# I2C_Step_12V_List1.net
KiCad netlist of a schematic drawn in Altium Designer
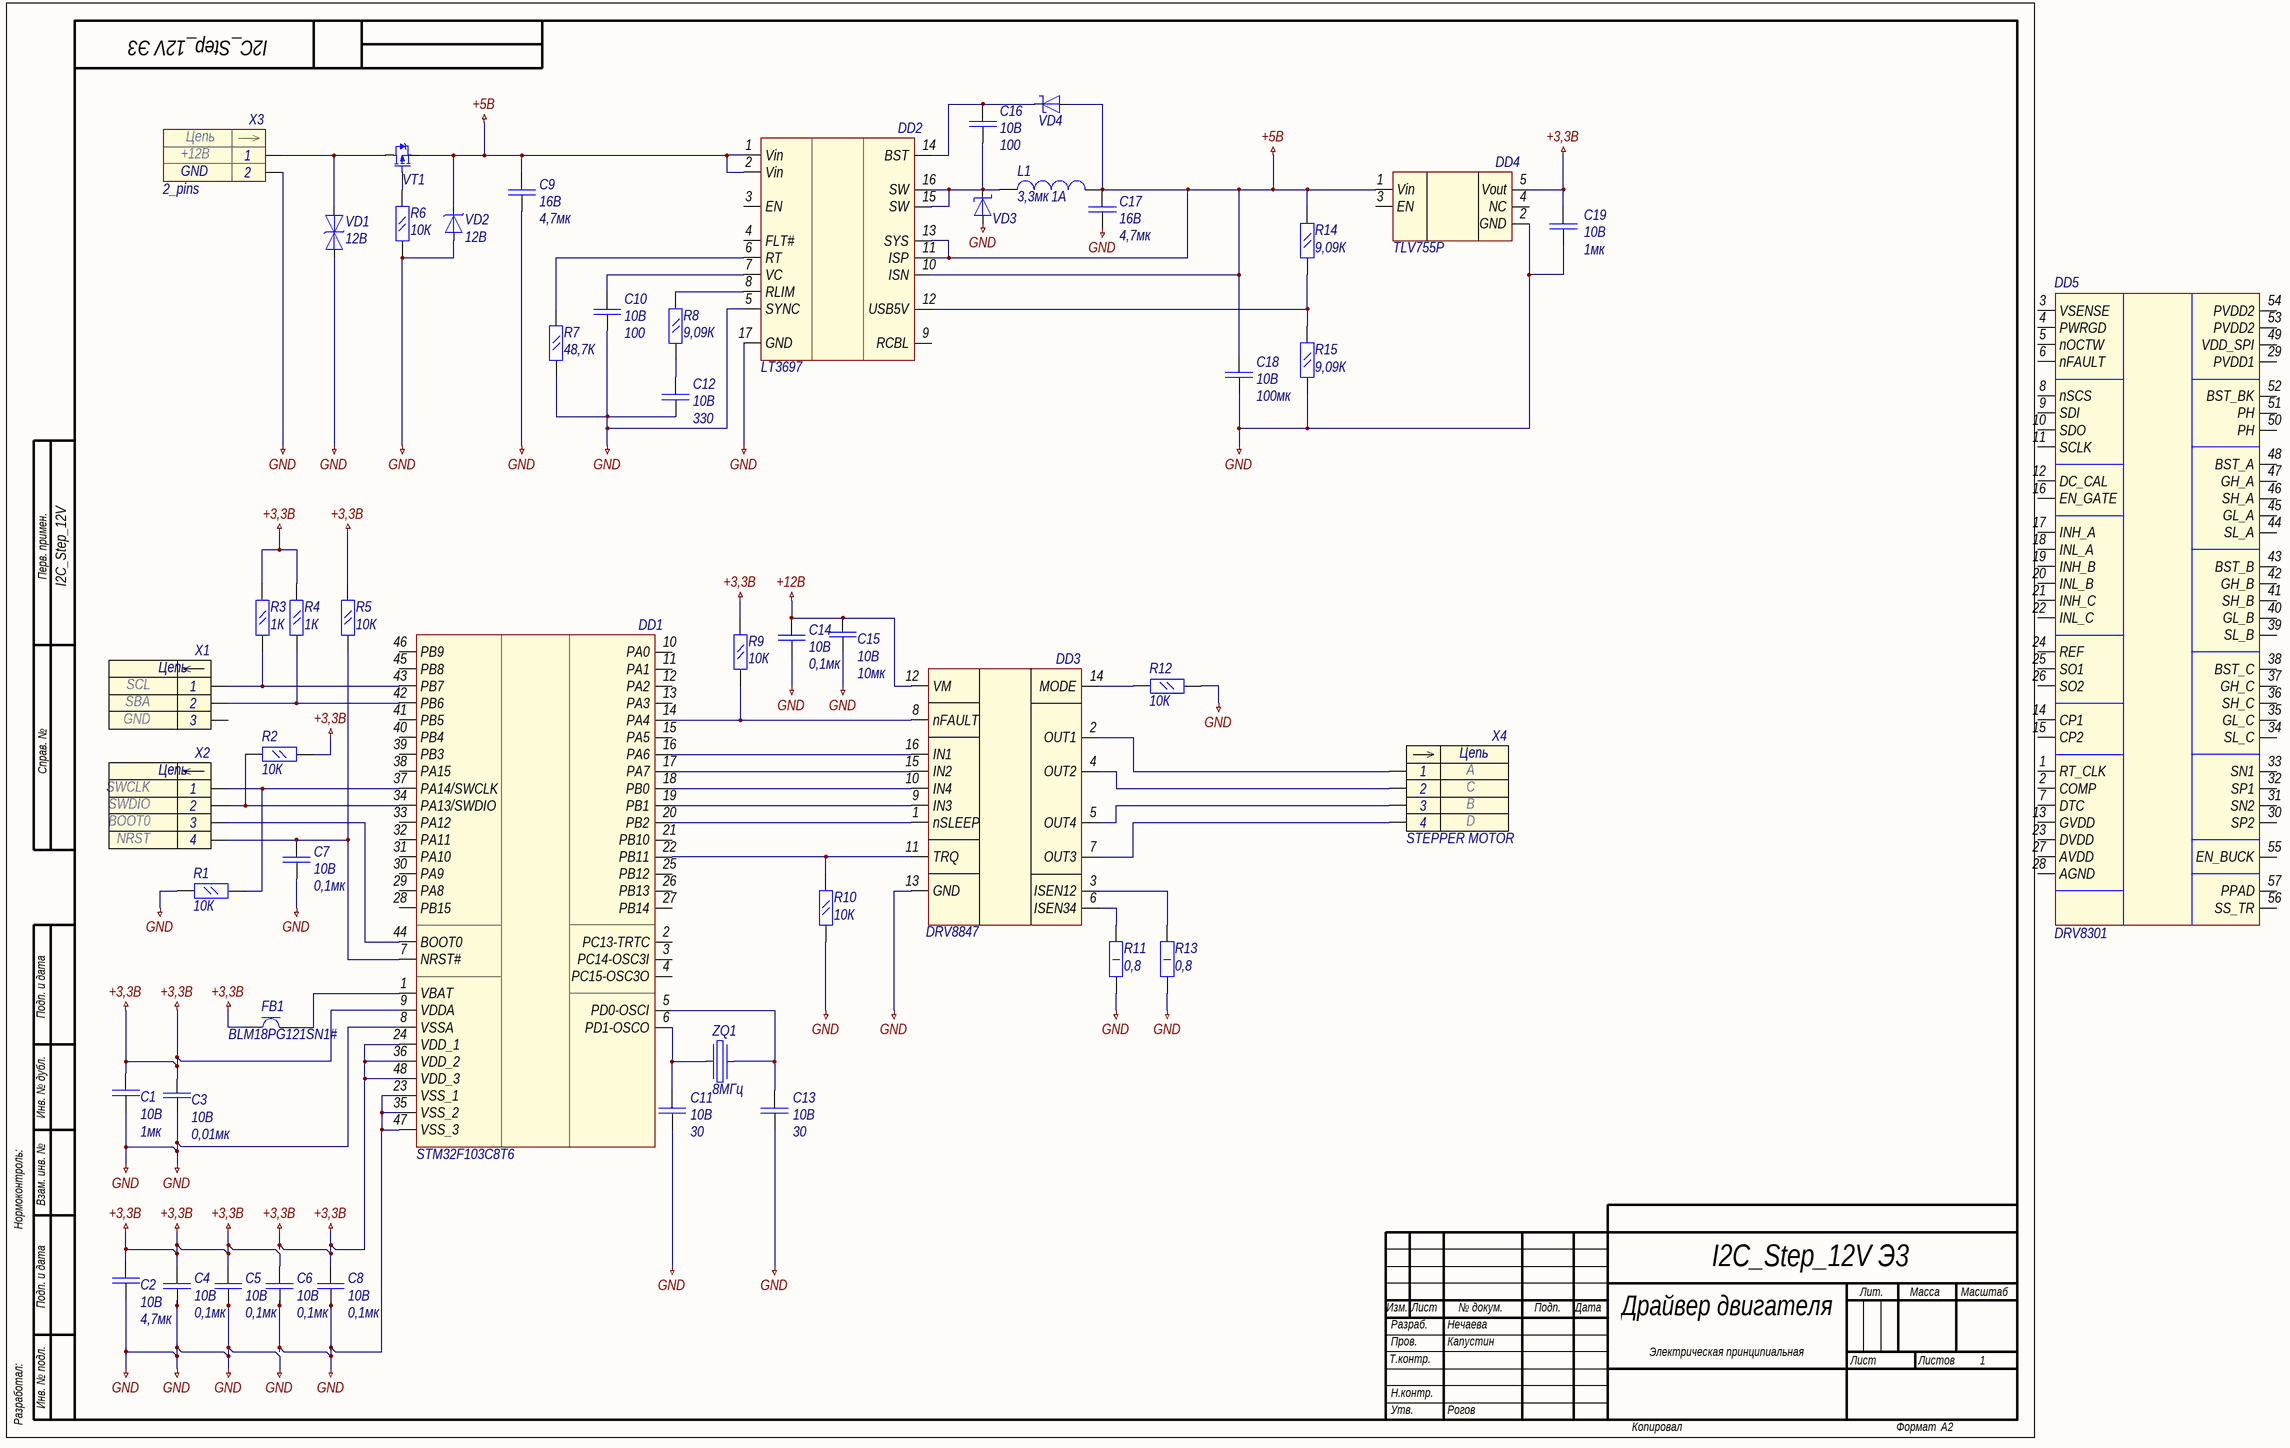
[diagram p0: I2C_Step_12V_List1.SchDoc]

(export (version "E")
  (design (tool "Eeschema 10.0.6"))
  (components
    (comp (ref "C1")
      (value "Capacitor")
      (footprint "CH0201C")
      (fields (field (name "VOLTAGE") "10В") (field (name "CAPACITANCE") "1мк"))
      (libsource (lib "GOST_Capacitors") (part "Capacitor"))
    )
    (comp (ref "C2")
      (value "Capacitor")
      (footprint "CH0402C")
      (fields (field (name "VOLTAGE") "10В") (field (name "CAPACITANCE") "4,7мк"))
      (libsource (lib "GOST_Capacitors") (part "Capacitor"))
    )
    (comp (ref "C3")
      (value "Capacitor")
      (footprint "CH0402C")
      (fields (field (name "VOLTAGE") "10В") (field (name "CAPACITANCE") "0,01мк"))
      (libsource (lib "") (part "Capacitor_1"))
    )
    (comp (ref "C4")
      (value "Capacitor")
      (footprint "CH0402C")
      (fields (field (name "VOLTAGE") "10В") (field (name "CAPACITANCE") "0,1мк"))
      (libsource (lib "GOST_Capacitors") (part "Capacitor"))
    )
    (comp (ref "C5")
      (value "Capacitor")
      (footprint "CH0402C")
      (fields (field (name "VOLTAGE") "10В") (field (name "CAPACITANCE") "0,1мк"))
      (libsource (lib "GOST_Capacitors") (part "Capacitor"))
    )
    (comp (ref "C6")
      (value "Capacitor")
      (footprint "CH0402C")
      (fields (field (name "VOLTAGE") "10В") (field (name "CAPACITANCE") "0,1мк"))
      (libsource (lib "GOST_Capacitors") (part "Capacitor"))
    )
    (comp (ref "C7")
      (value "Capacitor")
      (footprint "CH0402C")
      (fields (field (name "VOLTAGE") "10В") (field (name "CAPACITANCE") "0,1мк"))
      (libsource (lib "GOST_Capacitors") (part "Capacitor"))
    )
    (comp (ref "C8")
      (value "Capacitor")
      (footprint "CH0402C")
      (fields (field (name "VOLTAGE") "10В") (field (name "CAPACITANCE") "0,1мк"))
      (libsource (lib "GOST_Capacitors") (part "Capacitor"))
    )
    (comp (ref "C9")
      (value "Capacitor")
      (footprint "CH0603C")
      (fields (field (name "VOLTAGE") "16В") (field (name "CAPACITANCE") "4,7мк"))
      (libsource (lib "GOST_Capacitors") (part "Capacitor"))
    )
    (comp (ref "C10")
      (value "Capacitor")
      (footprint "CH0201C")
      (fields (field (name "VOLTAGE") "10В") (field (name "CAPACITANCE") "100"))
      (libsource (lib "GOST_Capacitors") (part "Capacitor"))
    )
    (comp (ref "C11")
      (value "Capacitor")
      (footprint "CH0201C")
      (fields (field (name "VOLTAGE") "10В") (field (name "CAPACITANCE") "30"))
      (libsource (lib "GOST_Capacitors") (part "Capacitor"))
    )
    (comp (ref "C12")
      (value "Capacitor")
      (footprint "CH0402C")
      (fields (field (name "VOLTAGE") "10В") (field (name "CAPACITANCE") "330"))
      (libsource (lib "GOST_Capacitors") (part "Capacitor"))
    )
    (comp (ref "C13")
      (value "Capacitor")
      (footprint "CH0201C")
      (fields (field (name "VOLTAGE") "10В") (field (name "CAPACITANCE") "30"))
      (libsource (lib "GOST_Capacitors") (part "Capacitor"))
    )
    (comp (ref "C14")
      (value "Capacitor")
      (footprint "CH0402C")
      (fields (field (name "VOLTAGE") "10В") (field (name "CAPACITANCE") "0,1мк"))
      (libsource (lib "GOST_Capacitors") (part "Capacitor"))
    )
    (comp (ref "C15")
      (value "Capacitor")
      (footprint "CH0402C")
      (fields (field (name "VOLTAGE") "10В") (field (name "CAPACITANCE") "10мк"))
      (libsource (lib "") (part "Capacitor_1"))
    )
    (comp (ref "C16")
      (value "Capacitor")
      (footprint "CH0201C")
      (fields (field (name "VOLTAGE") "10В") (field (name "CAPACITANCE") "100"))
      (libsource (lib "GOST_Capacitors") (part "Capacitor"))
    )
    (comp (ref "C17")
      (value "Capacitor")
      (footprint "CH0603C")
      (fields (field (name "VOLTAGE") "16В") (field (name "CAPACITANCE") "4,7мк"))
      (libsource (lib "GOST_Capacitors") (part "Capacitor"))
    )
    (comp (ref "C18")
      (value "Capacitor")
      (footprint "CH1206C")
      (fields (field (name "VOLTAGE") "10В") (field (name "CAPACITANCE") "100мк"))
      (libsource (lib "GOST_Capacitors") (part "Capacitor"))
    )
    (comp (ref "C19")
      (value "Capacitor")
      (footprint "CH0201C")
      (fields (field (name "VOLTAGE") "10В") (field (name "CAPACITANCE") "1мк"))
      (libsource (lib "GOST_Capacitors") (part "Capacitor"))
    )
    (comp (ref "DD1")
      (value "STM32F103C8T6")
      (footprint "STM32F103 48pins")
      (libsource (lib "GOST_lib_devices") (part "STM32"))
    )
    (comp (ref "DD2")
      (value "LT3697")
      (footprint "LT3697")
      (description "6~18 to 5")
      (libsource (lib "GOST_lib_devices") (part "LT3697"))
    )
    (comp (ref "DD3") (value "DRV8847") (libsource (lib "GOST_lib_devices") (part "DRV8847")))
    (comp (ref "DD4")
      (value "TLV755P")
      (footprint "SOT23-5")
      (libsource (lib "GOST_lib_devices") (part "LDO +3.3V"))
    )
    (comp (ref "DD5") (value "DRV8301") (libsource (lib "GOST_lib_devices") (part "DRV8301")))
    (comp (ref "FB1")
      (value "Ferrite bead")
      (footprint "CH0603L")
      (fields (field (name "MODEL") "BLM18PG121SN1#"))
      (libsource (lib "GOST_Inductors") (part "Ferrite bead"))
    )
    (comp (ref "L1")
      (value "*")
      (footprint "CH0805L")
      (fields (field (name "MAX CURRENT") "1А") (field (name "INDUCTANCE") "3,3мк"))
      (libsource (lib "GOST_Inductors") (part "Inductor"))
    )
    (comp (ref "R1")
      (value "Res_0.125")
      (footprint "CH0402R")
      (fields (field (name "IMPEDANCE") "10К"))
      (libsource (lib "GOST_Resistors") (part "Res_0.125"))
    )
    (comp (ref "R2")
      (value "Res_0.125")
      (footprint "CH0402R")
      (fields (field (name "IMPEDANCE") "10К"))
      (libsource (lib "GOST_Resistors") (part "Res_0.125"))
    )
    (comp (ref "R3")
      (value "Res_0.125")
      (footprint "CH0402R")
      (fields (field (name "IMPEDANCE") "1К"))
      (libsource (lib "GOST_Resistors") (part "Res_0.125"))
    )
    (comp (ref "R4")
      (value "Res_0.125")
      (footprint "CH0402R")
      (fields (field (name "IMPEDANCE") "1К"))
      (libsource (lib "GOST_Resistors") (part "Res_0.125"))
    )
    (comp (ref "R5")
      (value "Res_0.125")
      (footprint "CH0402R")
      (fields (field (name "IMPEDANCE") "10К"))
      (libsource (lib "GOST_Resistors") (part "Res_0.125"))
    )
    (comp (ref "R6")
      (value "Res_0.125")
      (footprint "CH0402R")
      (fields (field (name "IMPEDANCE") "10К"))
      (libsource (lib "GOST_Resistors") (part "Res_0.125"))
    )
    (comp (ref "R7")
      (value "Res_0.125")
      (footprint "CH0805R")
      (fields (field (name "IMPEDANCE") "48,7К"))
      (libsource (lib "GOST_Resistors") (part "Res_0.125"))
    )
    (comp (ref "R8")
      (value "Res_0.125")
      (footprint "CH0805R")
      (fields (field (name "IMPEDANCE") "9,09К"))
      (libsource (lib "GOST_Resistors") (part "Res_0.125"))
    )
    (comp (ref "R9")
      (value "Res_0.125")
      (footprint "CH0402R")
      (fields (field (name "IMPEDANCE") "10К"))
      (libsource (lib "GOST_Resistors") (part "Res_0.125"))
    )
    (comp (ref "R10")
      (value "Res_0.125")
      (footprint "CH0402R")
      (fields (field (name "IMPEDANCE") "10К"))
      (libsource (lib "GOST_Resistors") (part "Res_0.125"))
    )
    (comp (ref "R11")
      (value "Res_1")
      (footprint "CH2010R")
      (fields (field (name "POWER") "1Вт") (field (name "IMPEDANCE") "0,8"))
      (libsource (lib "GOST_Resistors") (part "Res_1"))
    )
    (comp (ref "R12")
      (value "Res_0.125")
      (footprint "CH0402R")
      (fields (field (name "IMPEDANCE") "10К"))
      (libsource (lib "GOST_Resistors") (part "Res_0.125"))
    )
    (comp (ref "R13")
      (value "Res_1")
      (footprint "CH2010R")
      (fields (field (name "POWER") "1Вт") (field (name "IMPEDANCE") "0,8"))
      (libsource (lib "GOST_Resistors") (part "Res_1"))
    )
    (comp (ref "R14")
      (value "Res_0.125")
      (footprint "CH0805R")
      (fields (field (name "IMPEDANCE") "9,09К"))
      (libsource (lib "GOST_Resistors") (part "Res_0.125"))
    )
    (comp (ref "R15")
      (value "Res_0.125")
      (footprint "CH0805R")
      (fields (field (name "IMPEDANCE") "9,09К"))
      (libsource (lib "GOST_Resistors") (part "Res_0.125"))
    )
    (comp (ref "VD1")
      (value "TVS-diod_simmetrical")
      (footprint "CH0201L")
      (fields (field (name "MANUFACTURER") "Littelfuse") (field (name "CLAMPING VOLTAGE") "12В"))
      (libsource (lib "GOST_Diodes") (part "TVS-diod_simmetrical"))
    )
    (comp (ref "VD2")
      (value "TVS-diod_directed")
      (footprint "DO214AA")
      (fields (field (name "MANUFACTURER") "Bourns") (field (name "CLAMPING_VOLTAGE") "12В"))
      (libsource (lib "GOST_Diodes") (part "TVS-diod_directed"))
    )
    (comp (ref "VD3")
      (value "Diod Schottky")
      (footprint "DO214AA")
      (fields (field (name "MANUFACTURER") "Rectron"))
      (libsource (lib "GOST_Diodes") (part "Diod Schottky"))
    )
    (comp (ref "VD4")
      (value "Diod Schottky")
      (footprint "SOT23_132")
      (fields (field (name "MANUFACTURER") "Toshiba"))
      (libsource (lib "GOST_Diodes") (part "Diod Schottky"))
    )
    (comp (ref "VT1")
      (value "*")
      (footprint "SOT23_132")
      (libsource (lib "GOST_Transistors") (part "P-Channel"))
    )
    (comp (ref "X1")
      (value "3_pins")
      (footprint "CON: PBS-3")
      (fields (field (name "2") "SBA") (field (name "3") "GND") (field (name "1") "SCL"))
      (libsource (lib "GOST_lib_connectors") (part "3_pins"))
    )
    (comp (ref "X2")
      (value "4_pins")
      (footprint "CON: CWF-4R")
      (fields
        (field (name "2") "SWDIO")
        (field (name "3") "BOOT0")
        (field (name "1") "SWCLK")
        (field (name "4") "NRST")
      )
      (libsource (lib "") (part "4_pins_1"))
    )
    (comp (ref "X3")
      (value "2_pins")
      (footprint "CON: 163-179PH-EX")
      (fields (field (name "VCC") "+12В"))
      (libsource (lib "GOST_lib_connectors") (part "2_pins"))
    )
    (comp (ref "X4")
      (value "STEPPER MOTOR")
      (footprint "CON: CWF-4R")
      (description "Bipolar Stepper Motor 200 Step 0.35A 12VDC")
      (fields (field (name "2") "C") (field (name "3") "B") (field (name "1") "A") (field (name "4") "D"))
      (libsource (lib "GOST_lib_connectors") (part "4_pins"))
    )
    (comp (ref "ZQ1")
      (value "Oscillator")
      (footprint "OSC: 5032")
      (fields (field (name "FREQ") "8МГц"))
      (libsource (lib "GOST_Miscelanuious") (part "Oscillator"))
    )
  )
  (nets
    (net (code "1") (name "+3,3В") (class "Default")
      (node (ref "C1") (pin "2") (pinfunction "C1-_2") (pintype "power_in"))
      (node (ref "C19") (pin "1") (pinfunction "C1+_1") (pintype "power_in"))
      (node (ref "C2") (pin "2") (pinfunction "C1-_2") (pintype "power_in"))
      (node (ref "C3") (pin "1") (pinfunction "С+_1") (pintype "power_in"))
      (node (ref "C4") (pin "1") (pinfunction "C1+_1") (pintype "power_in"))
      (node (ref "C5") (pin "1") (pinfunction "C1+_1") (pintype "power_in"))
      (node (ref "C6") (pin "1") (pinfunction "C1+_1") (pintype "power_in"))
      (node (ref "C8") (pin "1") (pinfunction "C1+_1") (pintype "power_in"))
      (node (ref "DD1") (pin "24") (pinfunction "VDD_1_24") (pintype "passive"))
      (node (ref "DD1") (pin "36") (pinfunction "VDD_2_36") (pintype "passive"))
      (node (ref "DD1") (pin "48") (pinfunction "VDD_3_48") (pintype "passive"))
      (node (ref "DD1") (pin "9") (pinfunction "VDDA_9") (pintype "passive"))
      (node (ref "DD4") (pin "5") (pinfunction "Vout_5") (pintype "power_in"))
      (node (ref "FB1") (pin "1") (pintype "power_in"))
      (node (ref "R2") (pin "1") (pinfunction "C1-_1") (pintype "power_in"))
      (node (ref "R3") (pin "1") (pinfunction "C1-_1") (pintype "power_in"))
      (node (ref "R4") (pin "1") (pinfunction "C1-_1") (pintype "power_in"))
      (node (ref "R5") (pin "1") (pinfunction "C1-_1") (pintype "power_in"))
      (node (ref "R9") (pin "1") (pinfunction "C1-_1") (pintype "power_in"))
    )
    (net (code "2") (name "+5В") (class "Default")
      (node (ref "C17") (pin "1") (pinfunction "C1+_1") (pintype "power_in"))
      (node (ref "C18") (pin "1") (pinfunction "C1+_1") (pintype "power_in"))
      (node (ref "C9") (pin "1") (pinfunction "C1+_1") (pintype "power_in"))
      (node (ref "DD2") (pin "1") (pinfunction "Vin_1") (pintype "power_in"))
      (node (ref "DD2") (pin "10") (pinfunction "ISN_10") (pintype "power_in"))
      (node (ref "DD2") (pin "11") (pinfunction "ISP_11") (pintype "power_in"))
      (node (ref "DD2") (pin "13") (pinfunction "SYS_13") (pintype "power_in"))
      (node (ref "DD2") (pin "2") (pinfunction "Vin_2") (pintype "power_in"))
      (node (ref "DD4") (pin "1") (pinfunction "Vin_1") (pintype "power_in"))
      (node (ref "L1") (pin "2") (pinfunction "14_2") (pintype "power_in"))
      (node (ref "R14") (pin "1") (pinfunction "C1-_1") (pintype "power_in"))
      (node (ref "VD2") (pin "2") (pinfunction "C_2") (pintype "passive"))
      (node (ref "VD4") (pin "1") (pinfunction "1_1") (pintype "passive"))
      (node (ref "VT1") (pin "3") (pinfunction "S_3") (pintype "passive"))
    )
    (net (code "3") (name "+12В") (class "Default")
      (node (ref "C14") (pin "1") (pinfunction "C1+_1") (pintype "power_in"))
      (node (ref "C15") (pin "1") (pinfunction "С+_1") (pintype "power_in"))
      (node (ref "DD3") (pin "12") (pinfunction "VM_12") (pintype "power_in"))
    )
    (net (code "4") (name "GND") (class "Default")
      (node (ref "C1") (pin "1") (pinfunction "C1+_1") (pintype "power_in"))
      (node (ref "C10") (pin "2") (pinfunction "C1-_2") (pintype "power_in"))
      (node (ref "C11") (pin "2") (pinfunction "C1-_2") (pintype "power_in"))
      (node (ref "C12") (pin "2") (pinfunction "C1-_2") (pintype "power_in"))
      (node (ref "C13") (pin "2") (pinfunction "C1-_2") (pintype "power_in"))
      (node (ref "C14") (pin "2") (pinfunction "C1-_2") (pintype "power_in"))
      (node (ref "C15") (pin "2") (pinfunction "С-_2") (pintype "power_in"))
      (node (ref "C17") (pin "2") (pinfunction "C1-_2") (pintype "power_in"))
      (node (ref "C18") (pin "2") (pinfunction "C1-_2") (pintype "power_in"))
      (node (ref "C19") (pin "2") (pinfunction "C1-_2") (pintype "power_in"))
      (node (ref "C2") (pin "1") (pinfunction "C1+_1") (pintype "power_in"))
      (node (ref "C3") (pin "2") (pinfunction "С-_2") (pintype "power_in"))
      (node (ref "C4") (pin "2") (pinfunction "C1-_2") (pintype "power_in"))
      (node (ref "C5") (pin "2") (pinfunction "C1-_2") (pintype "power_in"))
      (node (ref "C6") (pin "2") (pinfunction "C1-_2") (pintype "power_in"))
      (node (ref "C7") (pin "2") (pinfunction "C1-_2") (pintype "power_in"))
      (node (ref "C8") (pin "2") (pinfunction "C1-_2") (pintype "power_in"))
      (node (ref "C9") (pin "2") (pinfunction "C1-_2") (pintype "power_in"))
      (node (ref "DD1") (pin "23") (pinfunction "VSS_1_23") (pintype "passive"))
      (node (ref "DD1") (pin "35") (pinfunction "VSS_2_35") (pintype "passive"))
      (node (ref "DD1") (pin "47") (pinfunction "VSS_3_47") (pintype "passive"))
      (node (ref "DD1") (pin "8") (pinfunction "VSSA_8") (pintype "passive"))
      (node (ref "DD2") (pin "17") (pinfunction "GND_17") (pintype "power_in"))
      (node (ref "DD2") (pin "5") (pinfunction "SYNC_5") (pintype "power_in"))
      (node (ref "DD3") (pin "13") (pinfunction "GND_13") (pintype "power_in"))
      (node (ref "DD4") (pin "2") (pinfunction "GND_2") (pintype "power_in"))
      (node (ref "R1") (pin "2") (pinfunction "C1-_2") (pintype "power_in"))
      (node (ref "R10") (pin "2") (pinfunction "C1-_2") (pintype "power_in"))
      (node (ref "R11") (pin "1") (pinfunction "*_1") (pintype "power_in"))
      (node (ref "R12") (pin "1") (pinfunction "C1-_1") (pintype "power_in"))
      (node (ref "R13") (pin "1") (pinfunction "*_1") (pintype "power_in"))
      (node (ref "R15") (pin "2") (pinfunction "C1-_2") (pintype "power_in"))
      (node (ref "R6") (pin "1") (pinfunction "C1-_1") (pintype "power_in"))
      (node (ref "R7") (pin "2") (pinfunction "C1-_2") (pintype "power_in"))
      (node (ref "VD1") (pin "1") (pinfunction "A_1") (pintype "passive"))
      (node (ref "VD2") (pin "1") (pinfunction "A_1") (pintype "passive"))
      (node (ref "VD3") (pin "1") (pinfunction "1_1") (pintype "passive"))
      (node (ref "X3") (pin "2") (pinfunction "2_2") (pintype "passive"))
    )
    (net (code "5") (name "Net-(C7-C1+)") (class "Default")
      (node (ref "C7") (pin "1") (pinfunction "C1+_1") (pintype "power_in"))
      (node (ref "DD1") (pin "7") (pinfunction "NRST#_7") (pintype "passive"))
      (node (ref "R5") (pin "2") (pinfunction "C1-_2") (pintype "power_in"))
      (node (ref "X2") (pin "4") (pinfunction "4_4") (pintype "passive"))
    )
    (net (code "6") (name "Net-(C10-C1+)") (class "Default")
      (node (ref "C10") (pin "1") (pinfunction "C1+_1") (pintype "power_in"))
      (node (ref "DD2") (pin "7") (pinfunction "VC_7") (pintype "power_in"))
    )
    (net (code "7") (name "Net-(C11-C1+)") (class "Default")
      (node (ref "C11") (pin "1") (pinfunction "C1+_1") (pintype "power_in"))
      (node (ref "DD1") (pin "6") (pinfunction "PD1-OSCO_6") (pintype "passive"))
      (node (ref "ZQ1") (pin "1") (pintype "passive"))
    )
    (net (code "8") (name "Net-(C12-C1+)") (class "Default")
      (node (ref "C12") (pin "1") (pinfunction "C1+_1") (pintype "power_in"))
      (node (ref "R8") (pin "2") (pinfunction "C1-_2") (pintype "power_in"))
    )
    (net (code "9") (name "Net-(C13-C1+)") (class "Default")
      (node (ref "C13") (pin "1") (pinfunction "C1+_1") (pintype "power_in"))
      (node (ref "DD1") (pin "5") (pinfunction "PD0-OSCI_5") (pintype "passive"))
      (node (ref "ZQ1") (pin "3") (pintype "passive"))
    )
    (net (code "10") (name "Net-(C16-C1+)") (class "Default")
      (node (ref "C16") (pin "1") (pinfunction "C1+_1") (pintype "power_in"))
      (node (ref "DD2") (pin "14") (pinfunction "BST_14") (pintype "power_in"))
      (node (ref "VD4") (pin "2") (pinfunction "2_2") (pintype "passive"))
    )
    (net (code "11") (name "Net-(C16-C1-)") (class "Default")
      (node (ref "C16") (pin "2") (pinfunction "C1-_2") (pintype "power_in"))
      (node (ref "DD2") (pin "15") (pinfunction "SW_15") (pintype "power_in"))
      (node (ref "DD2") (pin "16") (pinfunction "SW_16") (pintype "power_in"))
      (node (ref "L1") (pin "1") (pinfunction "C1-_1") (pintype "power_in"))
      (node (ref "VD3") (pin "2") (pinfunction "2_2") (pintype "passive"))
    )
    (net (code "12") (name "Net-(DD1-BOOT0)") (class "Default")
      (node (ref "DD1") (pin "44") (pinfunction "BOOT0_44") (pintype "passive"))
      (node (ref "X2") (pin "3") (pinfunction "3_3") (pintype "passive"))
    )
    (net (code "13") (name "Net-(DD1-PA4)") (class "Default")
      (node (ref "DD1") (pin "14") (pinfunction "PA4_14") (pintype "passive"))
      (node (ref "DD3") (pin "8") (pinfunction "nFAULT_8") (pintype "power_in"))
      (node (ref "R9") (pin "2") (pinfunction "C1-_2") (pintype "power_in"))
    )
    (net (code "14") (name "Net-(DD1-PA6)") (class "Default")
      (node (ref "DD1") (pin "16") (pinfunction "PA6_16") (pintype "passive"))
      (node (ref "DD3") (pin "16") (pinfunction "IN1_16") (pintype "power_in"))
    )
    (net (code "15") (name "Net-(DD1-PA7)") (class "Default")
      (node (ref "DD1") (pin "17") (pinfunction "PA7_17") (pintype "passive"))
      (node (ref "DD3") (pin "15") (pinfunction "IN2_15") (pintype "power_in"))
    )
    (net (code "16") (name "Net-(DD1-PA13{slash}SWDIO)") (class "Default")
      (node (ref "DD1") (pin "34") (pinfunction "PA13/SWDIO_34") (pintype "passive"))
      (node (ref "R2") (pin "2") (pinfunction "C1-_2") (pintype "power_in"))
      (node (ref "X2") (pin "2") (pinfunction "2_2") (pintype "passive"))
    )
    (net (code "17") (name "Net-(DD1-PA14{slash}SWCLK)") (class "Default")
      (node (ref "DD1") (pin "37") (pinfunction "PA14/SWCLK_37") (pintype "passive"))
      (node (ref "R1") (pin "1") (pinfunction "C1-_1") (pintype "power_in"))
      (node (ref "X2") (pin "1") (pinfunction "1_1") (pintype "passive"))
    )
    (net (code "18") (name "Net-(DD1-PB0)") (class "Default")
      (node (ref "DD1") (pin "18") (pinfunction "PB0_18") (pintype "passive"))
      (node (ref "DD3") (pin "10") (pinfunction "IN4_10") (pintype "power_in"))
    )
    (net (code "19") (name "Net-(DD1-PB1)") (class "Default")
      (node (ref "DD1") (pin "19") (pinfunction "PB1_19") (pintype "passive"))
      (node (ref "DD3") (pin "9") (pinfunction "IN3_9") (pintype "power_in"))
    )
    (net (code "20") (name "Net-(DD1-PB2)") (class "Default")
      (node (ref "DD1") (pin "20") (pinfunction "PB2_20") (pintype "passive"))
      (node (ref "DD3") (pin "1") (pinfunction "nSLEEP_1") (pintype "power_in"))
    )
    (net (code "21") (name "Net-(DD1-PB6)") (class "Default")
      (node (ref "DD1") (pin "42") (pinfunction "PB6_42") (pintype "passive"))
      (node (ref "R4") (pin "2") (pinfunction "C1-_2") (pintype "power_in"))
      (node (ref "X1") (pin "2") (pinfunction "2_2") (pintype "passive"))
    )
    (net (code "22") (name "Net-(DD1-PB7)") (class "Default")
      (node (ref "DD1") (pin "43") (pinfunction "PB7_43") (pintype "passive"))
      (node (ref "R3") (pin "2") (pinfunction "C1-_2") (pintype "power_in"))
      (node (ref "X1") (pin "1") (pinfunction "1_1") (pintype "passive"))
    )
    (net (code "23") (name "Net-(DD1-PB11)") (class "Default")
      (node (ref "DD1") (pin "22") (pinfunction "PB11_22") (pintype "passive"))
      (node (ref "DD3") (pin "11") (pinfunction "TRQ_11") (pintype "power_in"))
      (node (ref "R10") (pin "1") (pinfunction "C1-_1") (pintype "power_in"))
    )
    (net (code "24") (name "Net-(DD1-VBAT)") (class "Default")
      (node (ref "DD1") (pin "1") (pinfunction "VBAT_1") (pintype "passive"))
      (node (ref "FB1") (pin "2") (pintype "power_in"))
    )
    (net (code "25") (name "Net-(DD2-RLIM)") (class "Default")
      (node (ref "DD2") (pin "8") (pinfunction "RLIM_8") (pintype "power_in"))
      (node (ref "R8") (pin "1") (pinfunction "C1-_1") (pintype "power_in"))
    )
    (net (code "26") (name "Net-(DD2-RT)") (class "Default")
      (node (ref "DD2") (pin "6") (pinfunction "RT_6") (pintype "power_in"))
      (node (ref "R7") (pin "1") (pinfunction "C1-_1") (pintype "power_in"))
    )
    (net (code "27") (name "Net-(DD2-USB5V)") (class "Default")
      (node (ref "DD2") (pin "12") (pinfunction "USB5V_12") (pintype "power_in"))
      (node (ref "R14") (pin "2") (pinfunction "C1-_2") (pintype "power_in"))
      (node (ref "R15") (pin "1") (pinfunction "C1-_1") (pintype "power_in"))
    )
    (net (code "28") (name "Net-(DD3-ISEN12)") (class "Default")
      (node (ref "DD3") (pin "3") (pinfunction "ISEN12_3") (pintype "power_in"))
      (node (ref "R13") (pin "2") (pinfunction "*_2") (pintype "power_in"))
    )
    (net (code "29") (name "Net-(DD3-ISEN34)") (class "Default")
      (node (ref "DD3") (pin "6") (pinfunction "ISEN34_6") (pintype "power_in"))
      (node (ref "R11") (pin "2") (pinfunction "*_2") (pintype "power_in"))
    )
    (net (code "30") (name "Net-(DD3-MODE)") (class "Default")
      (node (ref "DD3") (pin "14") (pinfunction "MODE_14") (pintype "power_in"))
      (node (ref "R12") (pin "2") (pinfunction "C1-_2") (pintype "power_in"))
    )
    (net (code "31") (name "Net-(DD3-OUT1)") (class "Default")
      (node (ref "DD3") (pin "2") (pinfunction "OUT1_2") (pintype "power_in"))
      (node (ref "X4") (pin "1") (pinfunction "1_1") (pintype "passive"))
    )
    (net (code "32") (name "Net-(DD3-OUT2)") (class "Default")
      (node (ref "DD3") (pin "4") (pinfunction "OUT2_4") (pintype "power_in"))
      (node (ref "X4") (pin "2") (pinfunction "2_2") (pintype "passive"))
    )
    (net (code "33") (name "Net-(DD3-OUT3)") (class "Default")
      (node (ref "DD3") (pin "7") (pinfunction "OUT3_7") (pintype "power_in"))
      (node (ref "X4") (pin "4") (pinfunction "4_4") (pintype "passive"))
    )
    (net (code "34") (name "Net-(DD3-OUT4)") (class "Default")
      (node (ref "DD3") (pin "5") (pinfunction "OUT4_5") (pintype "power_in"))
      (node (ref "X4") (pin "3") (pinfunction "3_3") (pintype "passive"))
    )
    (net (code "35") (name "Net-(VD1-C)") (class "Default")
      (node (ref "VD1") (pin "2") (pinfunction "C_2") (pintype "passive"))
      (node (ref "VT1") (pin "2") (pinfunction "D_2") (pintype "passive"))
      (node (ref "X3") (pin "1") (pinfunction "1_1") (pintype "passive"))
    )
    (net (code "36") (name "Net-(VT1-G)") (class "Default")
      (node (ref "R6") (pin "2") (pinfunction "C1-_2") (pintype "power_in"))
      (node (ref "VT1") (pin "1") (pinfunction "G_1") (pintype "passive"))
    )
    (net (code "37") (name "unconnected-(DD1-PA0-Pad10)") (class "Default")
      (node (ref "DD1") (pin "10") (pinfunction "PA0_10") (pintype "passive"))
    )
    (net (code "38") (name "unconnected-(DD1-PA1-Pad11)") (class "Default")
      (node (ref "DD1") (pin "11") (pinfunction "PA1_11") (pintype "passive"))
    )
    (net (code "39") (name "unconnected-(DD1-PA2-Pad12)") (class "Default")
      (node (ref "DD1") (pin "12") (pinfunction "PA2_12") (pintype "passive"))
    )
    (net (code "40") (name "unconnected-(DD1-PA3-Pad13)") (class "Default")
      (node (ref "DD1") (pin "13") (pinfunction "PA3_13") (pintype "passive"))
    )
    (net (code "41") (name "unconnected-(DD1-PA5-Pad15)") (class "Default")
      (node (ref "DD1") (pin "15") (pinfunction "PA5_15") (pintype "passive"))
    )
    (net (code "42") (name "unconnected-(DD1-PA8-Pad29)") (class "Default")
      (node (ref "DD1") (pin "29") (pinfunction "PA8_29") (pintype "passive"))
    )
    (net (code "43") (name "unconnected-(DD1-PA9-Pad30)") (class "Default")
      (node (ref "DD1") (pin "30") (pinfunction "PA9_30") (pintype "passive"))
    )
    (net (code "44") (name "unconnected-(DD1-PA10-Pad31)") (class "Default")
      (node (ref "DD1") (pin "31") (pinfunction "PA10_31") (pintype "passive"))
    )
    (net (code "45") (name "unconnected-(DD1-PA11-Pad32)") (class "Default")
      (node (ref "DD1") (pin "32") (pinfunction "PA11_32") (pintype "passive"))
    )
    (net (code "46") (name "unconnected-(DD1-PA12-Pad33)") (class "Default")
      (node (ref "DD1") (pin "33") (pinfunction "PA12_33") (pintype "passive"))
    )
    (net (code "47") (name "unconnected-(DD1-PA15-Pad38)") (class "Default")
      (node (ref "DD1") (pin "38") (pinfunction "PA15_38") (pintype "passive"))
    )
    (net (code "48") (name "unconnected-(DD1-PB3-Pad39)") (class "Default")
      (node (ref "DD1") (pin "39") (pinfunction "PB3_39") (pintype "passive"))
    )
    (net (code "49") (name "unconnected-(DD1-PB4-Pad40)") (class "Default")
      (node (ref "DD1") (pin "40") (pinfunction "PB4_40") (pintype "passive"))
    )
    (net (code "50") (name "unconnected-(DD1-PB5-Pad41)") (class "Default")
      (node (ref "DD1") (pin "41") (pinfunction "PB5_41") (pintype "passive"))
    )
    (net (code "51") (name "unconnected-(DD1-PB8-Pad45)") (class "Default")
      (node (ref "DD1") (pin "45") (pinfunction "PB8_45") (pintype "passive"))
    )
    (net (code "52") (name "unconnected-(DD1-PB9-Pad46)") (class "Default")
      (node (ref "DD1") (pin "46") (pinfunction "PB9_46") (pintype "passive"))
    )
    (net (code "53") (name "unconnected-(DD1-PB10-Pad21)") (class "Default")
      (node (ref "DD1") (pin "21") (pinfunction "PB10_21") (pintype "passive"))
    )
    (net (code "54") (name "unconnected-(DD1-PB12-Pad25)") (class "Default")
      (node (ref "DD1") (pin "25") (pinfunction "PB12_25") (pintype "passive"))
    )
    (net (code "55") (name "unconnected-(DD1-PB13-Pad26)") (class "Default")
      (node (ref "DD1") (pin "26") (pinfunction "PB13_26") (pintype "passive"))
    )
    (net (code "56") (name "unconnected-(DD1-PB14-Pad27)") (class "Default")
      (node (ref "DD1") (pin "27") (pinfunction "PB14_27") (pintype "passive"))
    )
    (net (code "57") (name "unconnected-(DD1-PB15-Pad28)") (class "Default")
      (node (ref "DD1") (pin "28") (pinfunction "PB15_28") (pintype "passive"))
    )
    (net (code "58") (name "unconnected-(DD1-PC13-TRTC-Pad2)") (class "Default")
      (node (ref "DD1") (pin "2") (pinfunction "PC13-TRTC_2") (pintype "passive"))
    )
    (net (code "59") (name "unconnected-(DD1-PC14-OSC3I-Pad3)") (class "Default")
      (node (ref "DD1") (pin "3") (pinfunction "PC14-OSC3I_3") (pintype "passive"))
    )
    (net (code "60") (name "unconnected-(DD1-PC15-OSC3O-Pad4)") (class "Default")
      (node (ref "DD1") (pin "4") (pinfunction "PC15-OSC3O_4") (pintype "passive"))
    )
    (net (code "61") (name "unconnected-(DD2-EN-Pad3)") (class "Default")
      (node (ref "DD2") (pin "3") (pinfunction "EN_3") (pintype "power_in"))
    )
    (net (code "62") (name "unconnected-(DD2-FLT#-Pad4)") (class "Default")
      (node (ref "DD2") (pin "4") (pinfunction "FLT#_4") (pintype "power_in"))
    )
    (net (code "63") (name "unconnected-(DD2-RCBL-Pad9)") (class "Default")
      (node (ref "DD2") (pin "9") (pinfunction "RCBL_9") (pintype "power_in"))
    )
    (net (code "64") (name "unconnected-(DD4-EN-Pad3)") (class "Default")
      (node (ref "DD4") (pin "3") (pinfunction "EN_3") (pintype "power_in"))
    )
    (net (code "65") (name "unconnected-(DD4-NC-Pad4)") (class "Default")
      (node (ref "DD4") (pin "4") (pinfunction "NC_4") (pintype "power_in"))
    )
    (net (code "66") (name "unconnected-(DD5-AGND-Pad28)") (class "Default")
      (node (ref "DD5") (pin "28") (pinfunction "AGND_28") (pintype "power_in"))
    )
    (net (code "67") (name "unconnected-(DD5-AVDD-Pad27)") (class "Default")
      (node (ref "DD5") (pin "27") (pinfunction "AVDD_27") (pintype "power_in"))
    )
    (net (code "68") (name "unconnected-(DD5-BST_A-Pad48)") (class "Default")
      (node (ref "DD5") (pin "48") (pinfunction "BST_A_48") (pintype "power_in"))
    )
    (net (code "69") (name "unconnected-(DD5-BST_B-Pad43)") (class "Default")
      (node (ref "DD5") (pin "43") (pinfunction "BST_B_43") (pintype "power_in"))
    )
    (net (code "70") (name "unconnected-(DD5-BST_BK-Pad52)") (class "Default")
      (node (ref "DD5") (pin "52") (pinfunction "BST_BK_52") (pintype "power_in"))
    )
    (net (code "71") (name "unconnected-(DD5-BST_C-Pad38)") (class "Default")
      (node (ref "DD5") (pin "38") (pinfunction "BST_C_38") (pintype "power_in"))
    )
    (net (code "72") (name "unconnected-(DD5-COMP-Pad2)") (class "Default")
      (node (ref "DD5") (pin "2") (pinfunction "COMP_2") (pintype "power_in"))
    )
    (net (code "73") (name "unconnected-(DD5-CP1-Pad14)") (class "Default")
      (node (ref "DD5") (pin "14") (pinfunction "CP1_14") (pintype "power_in"))
    )
    (net (code "74") (name "unconnected-(DD5-CP2-Pad15)") (class "Default")
      (node (ref "DD5") (pin "15") (pinfunction "CP2_15") (pintype "power_in"))
    )
    (net (code "75") (name "unconnected-(DD5-DC_CAL-Pad12)") (class "Default")
      (node (ref "DD5") (pin "12") (pinfunction "DC_CAL_12") (pintype "power_in"))
    )
    (net (code "76") (name "unconnected-(DD5-DTC-Pad7)") (class "Default")
      (node (ref "DD5") (pin "7") (pinfunction "DTC_7") (pintype "power_in"))
    )
    (net (code "77") (name "unconnected-(DD5-DVDD-Pad23)") (class "Default")
      (node (ref "DD5") (pin "23") (pinfunction "DVDD_23") (pintype "power_in"))
    )
    (net (code "78") (name "unconnected-(DD5-EN_BUCK-Pad55)") (class "Default")
      (node (ref "DD5") (pin "55") (pinfunction "EN_BUCK_55") (pintype "power_in"))
    )
    (net (code "79") (name "unconnected-(DD5-EN_GATE-Pad16)") (class "Default")
      (node (ref "DD5") (pin "16") (pinfunction "EN_GATE_16") (pintype "power_in"))
    )
    (net (code "80") (name "unconnected-(DD5-GH_A-Pad47)") (class "Default")
      (node (ref "DD5") (pin "47") (pinfunction "GH_A_47") (pintype "power_in"))
    )
    (net (code "81") (name "unconnected-(DD5-GH_B-Pad42)") (class "Default")
      (node (ref "DD5") (pin "42") (pinfunction "GH_B_42") (pintype "power_in"))
    )
    (net (code "82") (name "unconnected-(DD5-GH_C-Pad37)") (class "Default")
      (node (ref "DD5") (pin "37") (pinfunction "GH_C_37") (pintype "power_in"))
    )
    (net (code "83") (name "unconnected-(DD5-GL_A-Pad45)") (class "Default")
      (node (ref "DD5") (pin "45") (pinfunction "GL_A_45") (pintype "power_in"))
    )
    (net (code "84") (name "unconnected-(DD5-GL_B-Pad40)") (class "Default")
      (node (ref "DD5") (pin "40") (pinfunction "GL_B_40") (pintype "power_in"))
    )
    (net (code "85") (name "unconnected-(DD5-GL_C-Pad35)") (class "Default")
      (node (ref "DD5") (pin "35") (pinfunction "GL_C_35") (pintype "power_in"))
    )
    (net (code "86") (name "unconnected-(DD5-GVDD-Pad13)") (class "Default")
      (node (ref "DD5") (pin "13") (pinfunction "GVDD_13") (pintype "power_in"))
    )
    (net (code "87") (name "unconnected-(DD5-INH_A-Pad17)") (class "Default")
      (node (ref "DD5") (pin "17") (pinfunction "INH_A_17") (pintype "power_in"))
    )
    (net (code "88") (name "unconnected-(DD5-INH_B-Pad19)") (class "Default")
      (node (ref "DD5") (pin "19") (pinfunction "INH_B_19") (pintype "power_in"))
    )
    (net (code "89") (name "unconnected-(DD5-INH_C-Pad21)") (class "Default")
      (node (ref "DD5") (pin "21") (pinfunction "INH_C_21") (pintype "power_in"))
    )
    (net (code "90") (name "unconnected-(DD5-INL_A-Pad18)") (class "Default")
      (node (ref "DD5") (pin "18") (pinfunction "INL_A_18") (pintype "power_in"))
    )
    (net (code "91") (name "unconnected-(DD5-INL_B-Pad20)") (class "Default")
      (node (ref "DD5") (pin "20") (pinfunction "INL_B_20") (pintype "power_in"))
    )
    (net (code "92") (name "unconnected-(DD5-INL_C-Pad22)") (class "Default")
      (node (ref "DD5") (pin "22") (pinfunction "INL_C_22") (pintype "power_in"))
    )
    (net (code "93") (name "unconnected-(DD5-PH-Pad50)") (class "Default")
      (node (ref "DD5") (pin "50") (pinfunction "PH_50") (pintype "power_in"))
    )
    (net (code "94") (name "unconnected-(DD5-PH-Pad51)") (class "Default")
      (node (ref "DD5") (pin "51") (pinfunction "PH_51") (pintype "power_in"))
    )
    (net (code "95") (name "unconnected-(DD5-PPAD-Pad57)") (class "Default")
      (node (ref "DD5") (pin "57") (pinfunction "PPAD_57") (pintype "power_in"))
    )
    (net (code "96") (name "unconnected-(DD5-PVDD1-Pad29)") (class "Default")
      (node (ref "DD5") (pin "29") (pinfunction "PVDD1_29") (pintype "power_in"))
    )
    (net (code "97") (name "unconnected-(DD5-PVDD2-Pad53)") (class "Default")
      (node (ref "DD5") (pin "53") (pinfunction "PVDD2_53") (pintype "power_in"))
    )
    (net (code "98") (name "unconnected-(DD5-PVDD2-Pad54)") (class "Default")
      (node (ref "DD5") (pin "54") (pinfunction "PVDD2_54") (pintype "power_in"))
    )
    (net (code "99") (name "unconnected-(DD5-PWRGD-Pad4)") (class "Default")
      (node (ref "DD5") (pin "4") (pinfunction "PWRGD_4") (pintype "power_in"))
    )
    (net (code "100") (name "unconnected-(DD5-REF-Pad24)") (class "Default")
      (node (ref "DD5") (pin "24") (pinfunction "REF_24") (pintype "power_in"))
    )
    (net (code "101") (name "unconnected-(DD5-RT_CLK-Pad1)") (class "Default")
      (node (ref "DD5") (pin "1") (pinfunction "RT_CLK_1") (pintype "power_in"))
    )
    (net (code "102") (name "unconnected-(DD5-SCLK-Pad11)") (class "Default")
      (node (ref "DD5") (pin "11") (pinfunction "SCLK_11") (pintype "power_in"))
    )
    (net (code "103") (name "unconnected-(DD5-SDI-Pad9)") (class "Default")
      (node (ref "DD5") (pin "9") (pinfunction "SDI_9") (pintype "power_in"))
    )
    (net (code "104") (name "unconnected-(DD5-SDO-Pad10)") (class "Default")
      (node (ref "DD5") (pin "10") (pinfunction "SDO_10") (pintype "power_in"))
    )
    (net (code "105") (name "unconnected-(DD5-SH_A-Pad46)") (class "Default")
      (node (ref "DD5") (pin "46") (pinfunction "SH_A_46") (pintype "power_in"))
    )
    (net (code "106") (name "unconnected-(DD5-SH_B-Pad41)") (class "Default")
      (node (ref "DD5") (pin "41") (pinfunction "SH_B_41") (pintype "power_in"))
    )
    (net (code "107") (name "unconnected-(DD5-SH_C-Pad36)") (class "Default")
      (node (ref "DD5") (pin "36") (pinfunction "SH_C_36") (pintype "power_in"))
    )
    (net (code "108") (name "unconnected-(DD5-SL_A-Pad44)") (class "Default")
      (node (ref "DD5") (pin "44") (pinfunction "SL_A_44") (pintype "power_in"))
    )
    (net (code "109") (name "unconnected-(DD5-SL_B-Pad39)") (class "Default")
      (node (ref "DD5") (pin "39") (pinfunction "SL_B_39") (pintype "power_in"))
    )
    (net (code "110") (name "unconnected-(DD5-SL_C-Pad34)") (class "Default")
      (node (ref "DD5") (pin "34") (pinfunction "SL_C_34") (pintype "power_in"))
    )
    (net (code "111") (name "unconnected-(DD5-SN1-Pad33)") (class "Default")
      (node (ref "DD5") (pin "33") (pinfunction "SN1_33") (pintype "power_in"))
    )
    (net (code "112") (name "unconnected-(DD5-SN2-Pad31)") (class "Default")
      (node (ref "DD5") (pin "31") (pinfunction "SN2_31") (pintype "power_in"))
    )
    (net (code "113") (name "unconnected-(DD5-SO1-Pad25)") (class "Default")
      (node (ref "DD5") (pin "25") (pinfunction "SO1_25") (pintype "power_in"))
    )
    (net (code "114") (name "unconnected-(DD5-SO2-Pad26)") (class "Default")
      (node (ref "DD5") (pin "26") (pinfunction "SO2_26") (pintype "power_in"))
    )
    (net (code "115") (name "unconnected-(DD5-SP1-Pad32)") (class "Default")
      (node (ref "DD5") (pin "32") (pinfunction "SP1_32") (pintype "power_in"))
    )
    (net (code "116") (name "unconnected-(DD5-SP2-Pad30)") (class "Default")
      (node (ref "DD5") (pin "30") (pinfunction "SP2_30") (pintype "power_in"))
    )
    (net (code "117") (name "unconnected-(DD5-SS_TR-Pad56)") (class "Default")
      (node (ref "DD5") (pin "56") (pinfunction "SS_TR_56") (pintype "power_in"))
    )
    (net (code "118") (name "unconnected-(DD5-VDD_SPI-Pad49)") (class "Default")
      (node (ref "DD5") (pin "49") (pinfunction "VDD_SPI_49") (pintype "power_in"))
    )
    (net (code "119") (name "unconnected-(DD5-VSENSE-Pad3)") (class "Default")
      (node (ref "DD5") (pin "3") (pinfunction "VSENSE_3") (pintype "power_in"))
    )
    (net (code "120") (name "unconnected-(DD5-nFAULT-Pad6)") (class "Default")
      (node (ref "DD5") (pin "6") (pinfunction "nFAULT_6") (pintype "power_in"))
    )
    (net (code "121") (name "unconnected-(DD5-nOCTW-Pad5)") (class "Default")
      (node (ref "DD5") (pin "5") (pinfunction "nOCTW_5") (pintype "power_in"))
    )
    (net (code "122") (name "unconnected-(DD5-nSCS-Pad8)") (class "Default")
      (node (ref "DD5") (pin "8") (pinfunction "nSCS_8") (pintype "power_in"))
    )
    (net (code "123") (name "unconnected-(X1-Pad3)") (class "Default")
      (node (ref "X1") (pin "3") (pinfunction "3_3") (pintype "passive"))
    )
  )
)
